# sheet4_power.net
KiCad netlist of a schematic drawn in Altium Designer
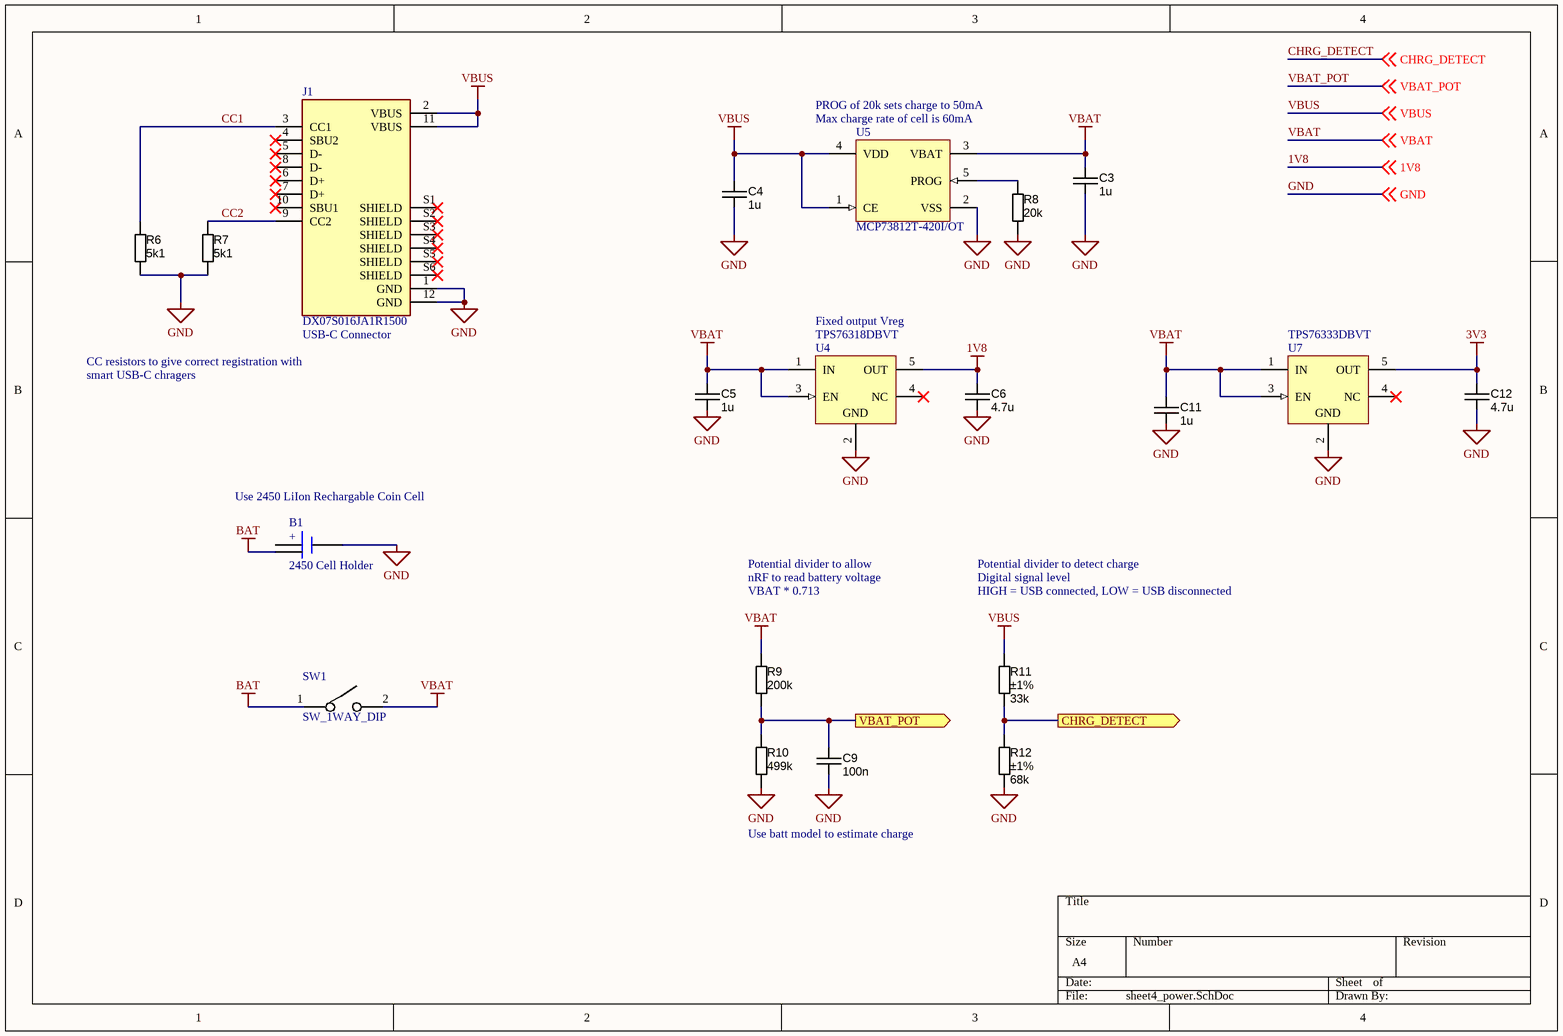
[diagram p0: sheet4_power.SchDoc]

(export (version "E")
  (design (tool "Eeschema 10.0.6"))
  (components
    (comp (ref "B1")
      (value "2450 Cell Holder")
      (footprint "BC-2404")
      (description "Multicomp BC-2404")
      (libsource (lib "Light Sensor Prototype") (part "2450-LiIon"))
    )
    (comp (ref "C3")
      (value "1u")
      (footprint "CAPC1005X55N")
      (description "Capacitor SMD Cer 1uF 10% 16V X5R 0402")
      (fields (field (name "TOLERANCE") "±10%"))
      (libsource (lib "Libs_RRutledge") (part "CAPC_100n_0402_X5R_16V_10%"))
    )
    (comp (ref "C4")
      (value "1u")
      (footprint "CAPC1005X55N")
      (description "Capacitor SMD Cer 1uF 10% 16V X5R 0402")
      (fields (field (name "TOLERANCE") "±10%"))
      (libsource (lib "Libs_RRutledge") (part "CAPC_100n_0402_X5R_16V_10%"))
    )
    (comp (ref "C5")
      (value "1u")
      (footprint "CAPC1005X55N")
      (description "Capacitor SMD Cer 1uF 10% 16V X5R 0402")
      (fields (field (name "TOLERANCE") "±10%"))
      (libsource (lib "Libs_RRutledge") (part "CAPC_100n_0402_X5R_16V_10%"))
    )
    (comp (ref "C6")
      (value "4.7u")
      (footprint "CAPC1005X55N")
      (description "Capacitor SMD Cer 4.7uF 10% 16V X5R 0402")
      (fields (field (name "TOLERANCE") "±10%"))
      (libsource (lib "Libs_RRutledge") (part "CAPC_100n_0402_X5R_16V_10%"))
    )
    (comp (ref "C9")
      (value "100n")
      (footprint "CAPC1005X55N")
      (description "Capacitor SMD Cer 100nF 10% 16V X5R 0402")
      (fields (field (name "TOLERANCE") "±10%"))
      (libsource (lib "Libs_RRutledge") (part "CAPC_100n_0402_X5R_16V_10%"))
    )
    (comp (ref "C11")
      (value "1u")
      (footprint "CAPC1005X55N")
      (description "Capacitor SMD Cer 1uF 10% 16V X5R 0402")
      (fields (field (name "TOLERANCE") "±10%"))
      (libsource (lib "Libs_RRutledge") (part "CAPC_100n_0402_X5R_16V_10%"))
    )
    (comp (ref "C12")
      (value "4.7u")
      (footprint "CAPC1005X55N")
      (description "Capacitor SMD Cer 4.7uF 10% 16V X5R 0402")
      (fields (field (name "TOLERANCE") "±10%"))
      (libsource (lib "Libs_RRutledge") (part "CAPC_100n_0402_X5R_16V_10%"))
    )
    (comp (ref "J1")
      (value "DX07S016JA1R1500")
      (footprint "JAE_DX07S016JA1R1500")
      (fields (field (name "MF") "JAE Electronics"))
      (libsource (lib "DX07S016JA1R1500") (part "DX07S016JA1R1500"))
    )
    (comp (ref "R6")
      (value "5k1")
      (footprint "RESC1005X40N")
      (description "Resistor SMD chip 5.1k Ohm 0.063W 5% 0402")
      (fields (field (name "TOLERANCE") "±5%") (field (name "Comment") "Thick Film"))
      (libsource (lib "Libs_RRutledge") (part "RES_3K3_0402_5%"))
    )
    (comp (ref "R7")
      (value "5k1")
      (footprint "RESC1005X40N")
      (description "Resistor SMD chip 5.1k Ohm 0.063W 5% 0402")
      (fields (field (name "TOLERANCE") "±5%") (field (name "Comment") "Thick Film"))
      (libsource (lib "Libs_RRutledge") (part "RES_3K3_0402_5%"))
    )
    (comp (ref "R8")
      (value "20k")
      (footprint "RESC1005X40N")
      (description "Resistor SMD chip 20k Ohm 0.063W 5% 0402")
      (fields (field (name "TOLERANCE") "±5%") (field (name "Comment") "Thick Film"))
      (libsource (lib "Libs_RRutledge") (part "RES_3K3_0402_5%"))
    )
    (comp (ref "R9")
      (value "200k")
      (footprint "RESC1005X40N")
      (description "Resistor SMD chip 2.4 MOhm 0.063W 5% 0402")
      (fields (field (name "TOLERANCE") "±5%") (field (name "Comment") "Thick Film"))
      (libsource (lib "Libs_RRutledge") (part "RES_3K3_0402_5%"))
    )
    (comp (ref "R10")
      (value "499k")
      (footprint "RESC1005X40N")
      (description "Resistor SMD chip 7.5 MOhm 0.063W 5% 0402")
      (fields (field (name "TOLERANCE") "±5%") (field (name "Comment") "Thick Film"))
      (libsource (lib "Libs_RRutledge") (part "RES_3K3_0402_5%"))
    )
    (comp (ref "R11")
      (value "33k")
      (footprint "RESC1608X55N")
      (description "Resistor SMD chip 33k Ohm 0.1W 1% 0603")
      (fields (field (name "TOLERANCE") "±1%") (field (name "Comment") "Thick Film"))
      (libsource (lib "Libs_RRutledge") (part "RES_10K_0603_1%"))
    )
    (comp (ref "R12")
      (value "68k")
      (footprint "RESC1608X55N")
      (description "Resistor SMD chip 68k Ohm 0.1W 1% 0603")
      (fields (field (name "TOLERANCE") "±1%") (field (name "Comment") "Thick Film"))
      (libsource (lib "Libs_RRutledge") (part "RES_10K_0603_1%"))
    )
    (comp (ref "SW1")
      (value "SW_1WAY_DIP")
      (footprint "SW_1WAY")
      (libsource (lib "DFU Connectors") (part "SW_1WAY_DIP"))
    )
    (comp (ref "U4")
      (value "TPS76318DBVT")
      (footprint "TI-DBV5_N")
      (fields (field (name "MANUFACTURER") "Texas Instruments"))
      (libsource (lib "TI Power Management Linear Regulator Single Channel LDO (0-350mA)") (part "TPS76318DBVT"))
    )
    (comp (ref "U5")
      (value "MCP73812T-420I/OT")
      (footprint "SOT-23-OT5_N")
      (fields (field (name "MANUFACTURER") "Microchip"))
      (libsource (lib "Microchip Power Management Battery Management") (part "MCP73812T-420I/OT"))
    )
    (comp (ref "U7")
      (value "TPS76333DBVT")
      (footprint "TI-DBV5_N")
      (fields (field (name "MANUFACTURER") "Texas Instruments"))
      (libsource (lib "TI Power Management Linear Regulator Single Channel LDO (0-350mA)") (part "TPS76333DBVT"))
    )
  )
  (nets
    (net (code "1") (name "/CC1") (class "Default")
      (node (ref "J1") (pin "3") (pinfunction "CC1_3") (pintype "passive"))
      (node (ref "R6") (pin "1") (pinfunction "1_1") (pintype "passive"))
    )
    (net (code "2") (name "/CC2") (class "Default")
      (node (ref "J1") (pin "9") (pinfunction "CC2_9") (pintype "passive"))
      (node (ref "R7") (pin "1") (pinfunction "1_1") (pintype "passive"))
    )
    (net (code "3") (name "1V8") (class "Default")
      (node (ref "C6") (pin "1") (pintype "passive"))
      (node (ref "U4") (pin "5") (pinfunction "OUT_5") (pintype "power_in"))
    )
    (net (code "4") (name "3V3") (class "Default")
      (node (ref "C12") (pin "1") (pintype "passive"))
      (node (ref "U7") (pin "5") (pinfunction "OUT_5") (pintype "power_in"))
    )
    (net (code "5") (name "BAT") (class "Default")
      (node (ref "B1") (pin "3") (pinfunction "+_3") (pintype "passive"))
      (node (ref "SW1") (pin "1") (pinfunction "1_1") (pintype "passive"))
    )
    (net (code "6") (name "CHRG_DETECT") (class "Default")
      (node (ref "R11") (pin "2") (pinfunction "2_2") (pintype "passive"))
      (node (ref "R12") (pin "1") (pinfunction "1_1") (pintype "passive"))
    )
    (net (code "7") (name "GND") (class "Default")
      (node (ref "B1") (pin "2") (pinfunction "-_2") (pintype "passive"))
      (node (ref "C11") (pin "2") (pintype "passive"))
      (node (ref "C12") (pin "2") (pintype "passive"))
      (node (ref "C3") (pin "2") (pintype "passive"))
      (node (ref "C4") (pin "2") (pintype "passive"))
      (node (ref "C5") (pin "2") (pintype "passive"))
      (node (ref "C6") (pin "2") (pintype "passive"))
      (node (ref "C9") (pin "2") (pintype "passive"))
      (node (ref "J1") (pin "1") (pinfunction "GND_1") (pintype "power_in"))
      (node (ref "J1") (pin "12") (pinfunction "GND_12") (pintype "power_in"))
      (node (ref "R10") (pin "2") (pinfunction "2_2") (pintype "passive"))
      (node (ref "R12") (pin "2") (pinfunction "2_2") (pintype "passive"))
      (node (ref "R6") (pin "2") (pinfunction "2_2") (pintype "passive"))
      (node (ref "R7") (pin "2") (pinfunction "2_2") (pintype "passive"))
      (node (ref "R8") (pin "2") (pinfunction "2_2") (pintype "passive"))
      (node (ref "U4") (pin "2") (pinfunction "GND_2") (pintype "power_in"))
      (node (ref "U5") (pin "2") (pinfunction "VSS_2") (pintype "power_in"))
      (node (ref "U7") (pin "2") (pinfunction "GND_2") (pintype "power_in"))
    )
    (net (code "8") (name "Net-(U5-PROG)") (class "Default")
      (node (ref "R8") (pin "1") (pinfunction "1_1") (pintype "passive"))
      (node (ref "U5") (pin "5") (pinfunction "PROG_5") (pintype "input"))
    )
    (net (code "9") (name "VBAT") (class "Default")
      (node (ref "C11") (pin "1") (pintype "passive"))
      (node (ref "C3") (pin "1") (pintype "passive"))
      (node (ref "C5") (pin "1") (pintype "passive"))
      (node (ref "R9") (pin "1") (pinfunction "1_1") (pintype "passive"))
      (node (ref "SW1") (pin "2") (pinfunction "2_2") (pintype "passive"))
      (node (ref "U4") (pin "1") (pinfunction "IN_1") (pintype "power_in"))
      (node (ref "U4") (pin "3") (pinfunction "EN_3") (pintype "input"))
      (node (ref "U5") (pin "3") (pinfunction "VBAT_3") (pintype "power_in"))
      (node (ref "U7") (pin "1") (pinfunction "IN_1") (pintype "power_in"))
      (node (ref "U7") (pin "3") (pinfunction "EN_3") (pintype "input"))
    )
    (net (code "10") (name "VBAT_POT") (class "Default")
      (node (ref "C9") (pin "1") (pintype "passive"))
      (node (ref "R10") (pin "1") (pinfunction "1_1") (pintype "passive"))
      (node (ref "R9") (pin "2") (pinfunction "2_2") (pintype "passive"))
    )
    (net (code "11") (name "VBUS") (class "Default")
      (node (ref "C4") (pin "1") (pintype "passive"))
      (node (ref "J1") (pin "11") (pinfunction "VBUS_11") (pintype "power_in"))
      (node (ref "J1") (pin "2") (pinfunction "VBUS_2") (pintype "power_in"))
      (node (ref "R11") (pin "1") (pinfunction "1_1") (pintype "passive"))
      (node (ref "U5") (pin "1") (pinfunction "CE_1") (pintype "input"))
      (node (ref "U5") (pin "4") (pinfunction "VDD_4") (pintype "power_in"))
    )
    (net (code "12") (name "unconnected-(B1-+-Pad1)") (class "Default")
      (node (ref "B1") (pin "1") (pinfunction "+_1") (pintype "passive"))
    )
    (net (code "13") (name "unconnected-(J1-D+-Pad6)") (class "Default")
      (node (ref "J1") (pin "6") (pinfunction "D+_6") (pintype "passive+no_connect"))
    )
    (net (code "14") (name "unconnected-(J1-D+-Pad7)") (class "Default")
      (node (ref "J1") (pin "7") (pinfunction "D+_7") (pintype "passive+no_connect"))
    )
    (net (code "15") (name "unconnected-(J1-D--Pad5)") (class "Default")
      (node (ref "J1") (pin "5") (pinfunction "D-_5") (pintype "passive+no_connect"))
    )
    (net (code "16") (name "unconnected-(J1-D--Pad8)") (class "Default")
      (node (ref "J1") (pin "8") (pinfunction "D-_8") (pintype "passive+no_connect"))
    )
    (net (code "17") (name "unconnected-(J1-SBU1-Pad10)") (class "Default")
      (node (ref "J1") (pin "10") (pinfunction "SBU1_10") (pintype "passive+no_connect"))
    )
    (net (code "18") (name "unconnected-(J1-SBU2-Pad4)") (class "Default")
      (node (ref "J1") (pin "4") (pinfunction "SBU2_4") (pintype "passive+no_connect"))
    )
    (net (code "19") (name "unconnected-(J1-SHIELD-PadS1)") (class "Default")
      (node (ref "J1") (pin "S1") (pinfunction "SHIELD_S1") (pintype "passive+no_connect"))
    )
    (net (code "20") (name "unconnected-(J1-SHIELD-PadS2)") (class "Default")
      (node (ref "J1") (pin "S2") (pinfunction "SHIELD_S2") (pintype "passive+no_connect"))
    )
    (net (code "21") (name "unconnected-(J1-SHIELD-PadS3)") (class "Default")
      (node (ref "J1") (pin "S3") (pinfunction "SHIELD_S3") (pintype "passive+no_connect"))
    )
    (net (code "22") (name "unconnected-(J1-SHIELD-PadS4)") (class "Default")
      (node (ref "J1") (pin "S4") (pinfunction "SHIELD_S4") (pintype "passive+no_connect"))
    )
    (net (code "23") (name "unconnected-(J1-SHIELD-PadS5)") (class "Default")
      (node (ref "J1") (pin "S5") (pinfunction "SHIELD_S5") (pintype "passive+no_connect"))
    )
    (net (code "24") (name "unconnected-(J1-SHIELD-PadS6)") (class "Default")
      (node (ref "J1") (pin "S6") (pinfunction "SHIELD_S6") (pintype "passive+no_connect"))
    )
    (net (code "25") (name "unconnected-(U4-NC-Pad4)") (class "Default")
      (node (ref "U4") (pin "4") (pinfunction "NC_4") (pintype "passive+no_connect"))
    )
    (net (code "26") (name "unconnected-(U7-NC-Pad4)") (class "Default")
      (node (ref "U7") (pin "4") (pinfunction "NC_4") (pintype "passive+no_connect"))
    )
  )
)
